# untitled.net
KiCad netlist of a schematic drawn in EAGLE
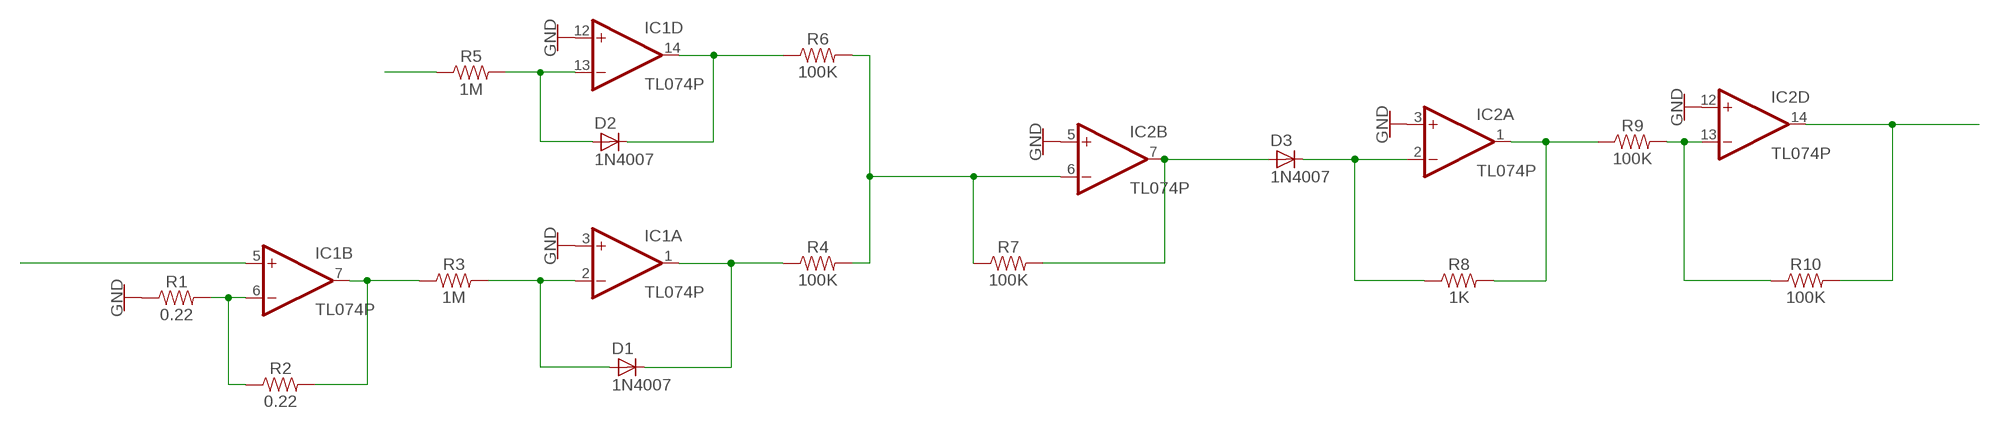
[diagram p0: schematic, sheet 1]

(export (version "E")
  (design (tool "Eeschema 10.0.6"))
  (components
    (comp (ref "D1")
      (value "1N4007")
      (footprint "eagle-import:SMA")
      (libsource (lib "eagle-import") (part "1N4007"))
    )
    (comp (ref "D2")
      (value "1N4007")
      (footprint "eagle-import:SMA")
      (libsource (lib "eagle-import") (part "1N4007"))
    )
    (comp (ref "D3")
      (value "1N4007")
      (footprint "eagle-import:SMA")
      (libsource (lib "eagle-import") (part "1N4007"))
    )
    (comp (ref "IC1")
      (value "TL074P")
      (footprint "eagle-import:DIL14")
      (libsource (lib "eagle-import") (part "TL074P"))
    )
    (comp (ref "IC2")
      (value "TL074P")
      (footprint "eagle-import:DIL14")
      (libsource (lib "eagle-import") (part "TL074P"))
    )
    (comp (ref "R1")
      (value "0.22")
      (footprint "eagle-import:0805")
      (libsource (lib "eagle-import") (part "0.22OHM-0805-1/4W-1%"))
    )
    (comp (ref "R2")
      (value "0.22")
      (footprint "eagle-import:0805")
      (libsource (lib "eagle-import") (part "0.22OHM-0805-1/4W-1%"))
    )
    (comp (ref "R3")
      (value "1M")
      (footprint "eagle-import:0805")
      (libsource (lib "eagle-import") (part "0.22OHM-0805-1/4W-1%"))
    )
    (comp (ref "R4")
      (value "100K")
      (footprint "eagle-import:0805")
      (libsource (lib "eagle-import") (part "0.22OHM-0805-1/4W-1%"))
    )
    (comp (ref "R5")
      (value "1M")
      (footprint "eagle-import:0805")
      (libsource (lib "eagle-import") (part "0.22OHM-0805-1/4W-1%"))
    )
    (comp (ref "R6")
      (value "100K")
      (footprint "eagle-import:0805")
      (libsource (lib "eagle-import") (part "0.22OHM-0805-1/4W-1%"))
    )
    (comp (ref "R7")
      (value "100K")
      (footprint "eagle-import:0805")
      (libsource (lib "eagle-import") (part "0.22OHM-0805-1/4W-1%"))
    )
    (comp (ref "R8")
      (value "1K")
      (footprint "eagle-import:0805")
      (libsource (lib "eagle-import") (part "0.22OHM-0805-1/4W-1%"))
    )
    (comp (ref "R9")
      (value "100K")
      (footprint "eagle-import:0805")
      (libsource (lib "eagle-import") (part "0.22OHM-0805-1/4W-1%"))
    )
    (comp (ref "R10")
      (value "100K")
      (footprint "eagle-import:0805")
      (libsource (lib "eagle-import") (part "0.22OHM-0805-1/4W-1%"))
    )
  )
  (nets
    (net (code "1") (name "GND") (class "Default")
      (node (ref "IC1") (pin "12") (pinfunction "+IN_12") (pintype "input"))
      (node (ref "IC1") (pin "3") (pinfunction "+IN_3") (pintype "input"))
      (node (ref "IC2") (pin "12") (pinfunction "+IN_12") (pintype "input"))
      (node (ref "IC2") (pin "3") (pinfunction "+IN_3") (pintype "input"))
      (node (ref "IC2") (pin "5") (pinfunction "+IN_5") (pintype "input"))
      (node (ref "R1") (pin "1") (pinfunction "1_1") (pintype "passive"))
    )
    (net (code "2") (name "Net-(D1-C)") (class "Default")
      (node (ref "D1") (pin "K") (pinfunction "C_K") (pintype "passive"))
      (node (ref "IC1") (pin "1") (pinfunction "OUT_1") (pintype "output"))
      (node (ref "R4") (pin "1") (pinfunction "1_1") (pintype "passive"))
    )
    (net (code "3") (name "Net-(D2-C)") (class "Default")
      (node (ref "D2") (pin "K") (pinfunction "C_K") (pintype "passive"))
      (node (ref "IC1") (pin "14") (pinfunction "OUT_14") (pintype "output"))
      (node (ref "R6") (pin "1") (pinfunction "1_1") (pintype "passive"))
    )
    (net (code "4") (name "Net-(D3-C)") (class "Default")
      (node (ref "D3") (pin "K") (pinfunction "C_K") (pintype "passive"))
      (node (ref "IC2") (pin "2") (pinfunction "-IN_2") (pintype "input"))
      (node (ref "R8") (pin "1") (pinfunction "1_1") (pintype "passive"))
    )
    (net (code "5") (name "Net-(IC1A--IN)") (class "Default")
      (node (ref "D1") (pin "A") (pinfunction "A_A") (pintype "passive"))
      (node (ref "IC1") (pin "2") (pinfunction "-IN_2") (pintype "input"))
      (node (ref "R3") (pin "2") (pinfunction "2_2") (pintype "passive"))
    )
    (net (code "6") (name "Net-(IC1B--IN)") (class "Default")
      (node (ref "IC1") (pin "6") (pinfunction "-IN_6") (pintype "input"))
      (node (ref "R1") (pin "2") (pinfunction "2_2") (pintype "passive"))
      (node (ref "R2") (pin "1") (pinfunction "1_1") (pintype "passive"))
    )
    (net (code "7") (name "Net-(IC1B-OUT)") (class "Default")
      (node (ref "IC1") (pin "7") (pinfunction "OUT_7") (pintype "output"))
      (node (ref "R2") (pin "2") (pinfunction "2_2") (pintype "passive"))
      (node (ref "R3") (pin "1") (pinfunction "1_1") (pintype "passive"))
    )
    (net (code "8") (name "Net-(IC1D--IN)") (class "Default")
      (node (ref "D2") (pin "A") (pinfunction "A_A") (pintype "passive"))
      (node (ref "IC1") (pin "13") (pinfunction "-IN_13") (pintype "input"))
      (node (ref "R5") (pin "2") (pinfunction "2_2") (pintype "passive"))
    )
    (net (code "9") (name "Net-(IC2A-OUT)") (class "Default")
      (node (ref "IC2") (pin "1") (pinfunction "OUT_1") (pintype "output"))
      (node (ref "R8") (pin "2") (pinfunction "2_2") (pintype "passive"))
      (node (ref "R9") (pin "1") (pinfunction "1_1") (pintype "passive"))
    )
    (net (code "10") (name "Net-(IC2B--IN)") (class "Default")
      (node (ref "IC2") (pin "6") (pinfunction "-IN_6") (pintype "input"))
      (node (ref "R4") (pin "2") (pinfunction "2_2") (pintype "passive"))
      (node (ref "R6") (pin "2") (pinfunction "2_2") (pintype "passive"))
      (node (ref "R7") (pin "1") (pinfunction "1_1") (pintype "passive"))
    )
    (net (code "11") (name "Net-(IC2B-OUT)") (class "Default")
      (node (ref "D3") (pin "A") (pinfunction "A_A") (pintype "passive"))
      (node (ref "IC2") (pin "7") (pinfunction "OUT_7") (pintype "output"))
      (node (ref "R7") (pin "2") (pinfunction "2_2") (pintype "passive"))
    )
    (net (code "12") (name "Net-(IC2D--IN)") (class "Default")
      (node (ref "IC2") (pin "13") (pinfunction "-IN_13") (pintype "input"))
      (node (ref "R10") (pin "1") (pinfunction "1_1") (pintype "passive"))
      (node (ref "R9") (pin "2") (pinfunction "2_2") (pintype "passive"))
    )
    (net (code "13") (name "Net-(IC2D-OUT)") (class "Default")
      (node (ref "IC2") (pin "14") (pinfunction "OUT_14") (pintype "output"))
      (node (ref "R10") (pin "2") (pinfunction "2_2") (pintype "passive"))
    )
    (net (code "14") (name "unconnected-(IC1B-+IN-Pad5)") (class "Default")
      (node (ref "IC1") (pin "5") (pinfunction "+IN_5") (pintype "input"))
    )
    (net (code "15") (name "unconnected-(R5-Pad1)") (class "Default")
      (node (ref "R5") (pin "1") (pinfunction "1_1") (pintype "passive"))
    )
  )
)
